# MXR1_v1.net
KiCad netlist of a schematic drawn in EAGLE
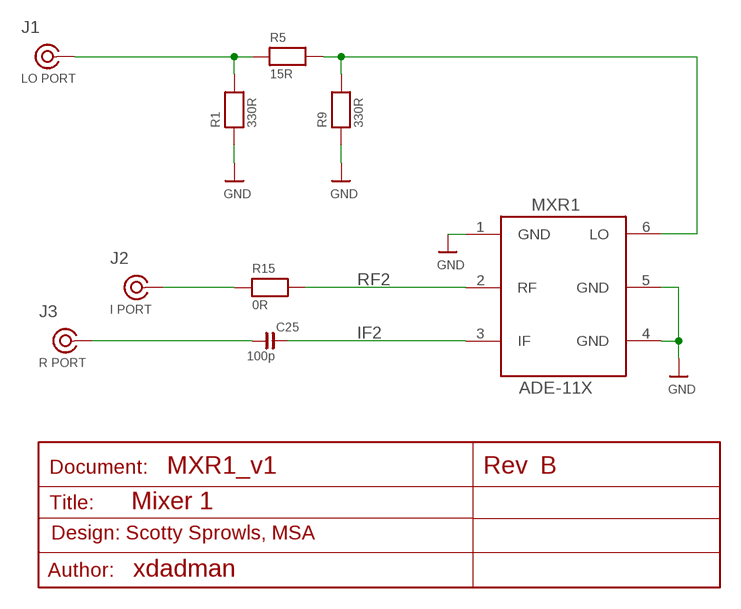
[diagram p0: schematic, sheet 1]

(export (version "E")
  (design (tool "Eeschema 10.0.6"))
  (components
    (comp (ref "C25")
      (value "100p")
      (footprint "eagle-import:C0805")
      (libsource (lib "eagle-import") (part "C0805100P"))
    )
    (comp (ref "J1")
      (value "LO PORT")
      (footprint "eagle-import:SLIM_COAX_PAD")
      (libsource (lib "eagle-import") (part "COAX"))
    )
    (comp (ref "J2")
      (value "I PORT")
      (footprint "eagle-import:SLIM_COAX_PAD")
      (libsource (lib "eagle-import") (part "COAX"))
    )
    (comp (ref "J3")
      (value "R PORT")
      (footprint "eagle-import:SLIM_COAX_PAD")
      (libsource (lib "eagle-import") (part "COAX"))
    )
    (comp (ref "MXR1")
      (value "ADE-11X")
      (footprint "eagle-import:ADE-11X")
      (libsource (lib "eagle-import") (part "ADE-11X"))
    )
    (comp (ref "R1")
      (value "330R")
      (footprint "eagle-import:R0805")
      (libsource (lib "eagle-import") (part "R0805330R"))
    )
    (comp (ref "R5")
      (value "15R")
      (footprint "eagle-import:0805")
      (libsource (lib "eagle-import") (part "R080515R"))
    )
    (comp (ref "R9")
      (value "330R")
      (footprint "eagle-import:R0805")
      (libsource (lib "eagle-import") (part "R0805330R"))
    )
    (comp (ref "R15")
      (value "0R")
      (footprint "eagle-import:R0805")
      (libsource (lib "eagle-import") (part "R08050R"))
    )
  )
  (nets
    (net (code "1") (name "/IF2") (class "Default")
      (node (ref "C25") (pin "2") (pinfunction "2_2") (pintype "passive"))
      (node (ref "MXR1") (pin "3") (pinfunction "IF_3") (pintype "bidirectional"))
    )
    (net (code "2") (name "/RF2") (class "Default")
      (node (ref "MXR1") (pin "2") (pinfunction "RF_2") (pintype "bidirectional"))
      (node (ref "R15") (pin "2") (pinfunction "2_2") (pintype "passive"))
    )
    (net (code "3") (name "GND") (class "Default")
      (node (ref "MXR1") (pin "1") (pinfunction "GND_1") (pintype "bidirectional"))
      (node (ref "MXR1") (pin "4") (pinfunction "GND_4") (pintype "bidirectional"))
      (node (ref "MXR1") (pin "5") (pinfunction "GND_5") (pintype "bidirectional"))
      (node (ref "R1") (pin "1") (pinfunction "1_1") (pintype "passive"))
      (node (ref "R9") (pin "1") (pinfunction "1_1") (pintype "passive"))
    )
    (net (code "4") (name "Net-(J1A-1)") (class "Default")
      (node (ref "J1") (pin "SIG") (pinfunction "1_SIG") (pintype "passive"))
      (node (ref "R1") (pin "2") (pinfunction "2_2") (pintype "passive"))
      (node (ref "R5") (pin "1") (pinfunction "1_1") (pintype "passive"))
    )
    (net (code "5") (name "Net-(J2A-1)") (class "Default")
      (node (ref "J2") (pin "SIG") (pinfunction "1_SIG") (pintype "passive"))
      (node (ref "R15") (pin "1") (pinfunction "1_1") (pintype "passive"))
    )
    (net (code "6") (name "Net-(J3A-1)") (class "Default")
      (node (ref "C25") (pin "1") (pinfunction "1_1") (pintype "passive"))
      (node (ref "J3") (pin "SIG") (pinfunction "1_SIG") (pintype "passive"))
    )
    (net (code "7") (name "Net-(MXR1-LO)") (class "Default")
      (node (ref "MXR1") (pin "6") (pinfunction "LO_6") (pintype "bidirectional"))
      (node (ref "R5") (pin "2") (pinfunction "2_2") (pintype "passive"))
      (node (ref "R9") (pin "2") (pinfunction "2_2") (pintype "passive"))
    )
  )
)
